# Atom_S3_Module_-_Rev_B.net
KiCad netlist of a schematic drawn in EAGLE
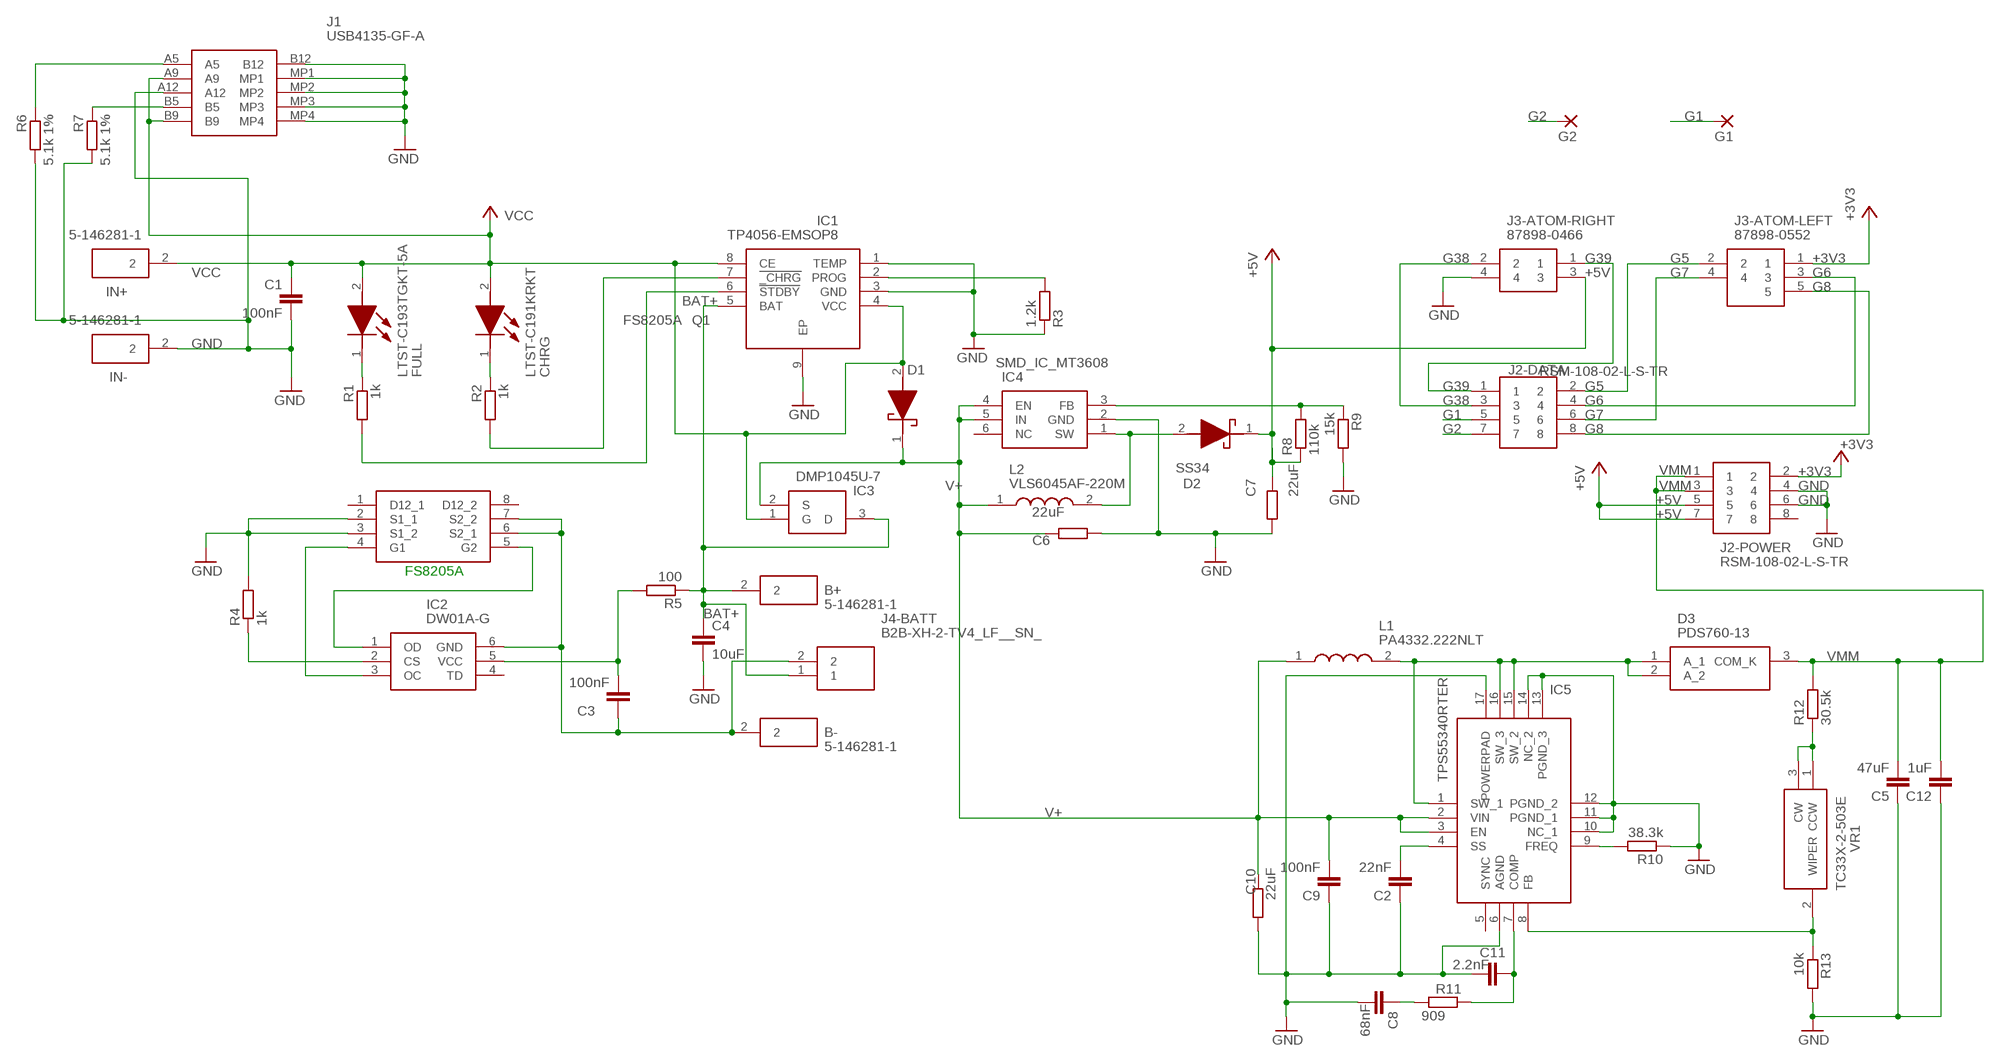
[diagram p0: schematic, sheet 1]

(export (version "E")
  (design (tool "Eeschema 10.0.6"))
  (components
    (comp (ref "B+")
      (value "5-146281-1")
      (footprint "eagle-import:51462811")
      (fields (field (name "MOUSER_PART_NUMBER") "571-5-146281-1"))
      (libsource (lib "eagle-import") (part "5-146281-1"))
    )
    (comp (ref "B-")
      (value "5-146281-1")
      (footprint "eagle-import:51462811")
      (fields (field (name "MOUSER_PART_NUMBER") "571-5-146281-1"))
      (libsource (lib "eagle-import") (part "5-146281-1"))
    )
    (comp (ref "C1")
      (value "100nF")
      (footprint "eagle-import:C0603")
      (libsource (lib "eagle-import") (part "C-EUC0603"))
    )
    (comp (ref "C2")
      (value "22nF")
      (footprint "eagle-import:C0603")
      (libsource (lib "eagle-import") (part "C-EUC0603"))
    )
    (comp (ref "C3")
      (value "100nF")
      (footprint "eagle-import:C0603")
      (libsource (lib "eagle-import") (part "C-EUC0603"))
    )
    (comp (ref "C4")
      (value "10uF")
      (footprint "eagle-import:C0603")
      (libsource (lib "eagle-import") (part "C-EUC0603"))
    )
    (comp (ref "C5")
      (value "47uF")
      (footprint "eagle-import:C1210")
      (libsource (lib "eagle-import") (part "C-EUC1210"))
    )
    (comp (ref "C6")
      (value "22uF")
      (footprint "eagle-import:R0805")
      (libsource (lib "eagle-import") (part "R-EU_R0805"))
    )
    (comp (ref "C7")
      (value "22uF")
      (footprint "eagle-import:R0805")
      (libsource (lib "eagle-import") (part "R-EU_R0805"))
    )
    (comp (ref "C8")
      (value "68nF")
      (footprint "eagle-import:C0603")
      (libsource (lib "eagle-import") (part "C-EUC0603"))
    )
    (comp (ref "C9")
      (value "100nF")
      (footprint "eagle-import:C0603")
      (libsource (lib "eagle-import") (part "C-EUC0603"))
    )
    (comp (ref "C10")
      (value "22uF")
      (footprint "eagle-import:R0805")
      (libsource (lib "eagle-import") (part "R-EU_R0805"))
    )
    (comp (ref "C11")
      (value "2.2nF")
      (footprint "eagle-import:C0603")
      (libsource (lib "eagle-import") (part "C-EUC0603"))
    )
    (comp (ref "C12")
      (value "1uF")
      (footprint "eagle-import:C0603")
      (libsource (lib "eagle-import") (part "C-EUC0603"))
    )
    (comp (ref "CHRG")
      (value "LTST-C191KRKT")
      (footprint "eagle-import:LEDC1608X55N")
      (fields (field (name "MOUSER_PART_NUMBER") "859-LTST-C191KRKT"))
      (libsource (lib "eagle-import") (part "LTST-C191KRKT"))
    )
    (comp (ref "D1")
      (value "SS34")
      (footprint "eagle-import:DIOM8059X256N")
      (fields (field (name "MOUSER_PART_NUMBER") "512-SS34"))
      (libsource (lib "eagle-import") (part "SS34"))
    )
    (comp (ref "D2")
      (value "SS34")
      (footprint "eagle-import:DIOM8059X256N")
      (fields (field (name "MOUSER_PART_NUMBER") "512-SS34"))
      (libsource (lib "eagle-import") (part "SS34"))
    )
    (comp (ref "D3")
      (value "PDS760-13")
      (footprint "eagle-import:PDS76013")
      (fields (field (name "MOUSER_PART_NUMBER") "621-PDS760-F"))
      (libsource (lib "eagle-import") (part "PDS760-13"))
    )
    (comp (ref "FULL")
      (value "LTST-C193TGKT-5A")
      (footprint "eagle-import:LEDC1608X45N")
      (fields (field (name "MOUSER_PART_NUMBER") "859-LTSTC193TGKT5A"))
      (libsource (lib "eagle-import") (part "LTST-C193TGKT-5A"))
    )
    (comp (ref "G1")
      (value "WIREPAD1,6/0,9")
      (footprint "eagle-import:1,6_0,9")
      (libsource (lib "eagle-import") (part "WIREPAD1,6/0,9"))
    )
    (comp (ref "G2")
      (value "WIREPAD1,6/0,9")
      (footprint "eagle-import:1,6_0,9")
      (libsource (lib "eagle-import") (part "WIREPAD1,6/0,9"))
    )
    (comp (ref "IC1")
      (value "TP4056-EMSOP8")
      (footprint "eagle-import:SOP65P490X110-9N")
      (libsource (lib "eagle-import") (part "TP4056-EMSOP8"))
    )
    (comp (ref "IC2")
      (value "DW01A-G")
      (footprint "eagle-import:SOT95P190X145-6N")
      (libsource (lib "eagle-import") (part "DW01A-G"))
    )
    (comp (ref "IC3")
      (value "DMP1045U-7")
      (footprint "eagle-import:SOT96P240X110-3N")
      (fields (field (name "MOUSER_PART_NUMBER") "621-DMP1045U-7"))
      (libsource (lib "eagle-import") (part "DMP1045U-7"))
    )
    (comp (ref "IC4")
      (value "SMD_IC_MT3608")
      (footprint "eagle-import:SOT95P280X145-6N")
      (fields
        (field (name "MANUFACTURER_PART_NUMBER") "SMD IC MT3608")
        (field (name "MOUSER_PART_NUMBER") "909-SMDICMT3608")
      )
      (libsource (lib "eagle-import") (part "SMD_IC_MT3608"))
    )
    (comp (ref "IC5")
      (value "TPS55340RTER")
      (footprint "eagle-import:QFN50P300X300X80-17N")
      (fields (field (name "MOUSER_PART_NUMBER") "595-TPS55340RTER"))
      (libsource (lib "eagle-import") (part "TPS55340RTER"))
    )
    (comp (ref "IN+")
      (value "5-146281-1")
      (footprint "eagle-import:51462811")
      (fields (field (name "MOUSER_PART_NUMBER") "571-5-146281-1"))
      (libsource (lib "eagle-import") (part "5-146281-1"))
    )
    (comp (ref "IN-")
      (value "5-146281-1")
      (footprint "eagle-import:51462811")
      (fields (field (name "MOUSER_PART_NUMBER") "571-5-146281-1"))
      (libsource (lib "eagle-import") (part "5-146281-1"))
    )
    (comp (ref "J1")
      (value "USB4135-GF-A")
      (footprint "eagle-import:USB4135GFA")
      (fields (field (name "MOUSER_PART_NUMBER") "640-USB4135-GF-A"))
      (libsource (lib "eagle-import") (part "USB4135-GF-A"))
    )
    (comp (ref "J2-DATA")
      (value "RSM-108-02-L-S-TR")
      (footprint "eagle-import:RSM10802LSTR")
      (fields (field (name "MOUSER_PART_NUMBER") "200-RSM10802LSTR"))
      (libsource (lib "eagle-import") (part "RSM-108-02-L-S-TR"))
    )
    (comp (ref "J2-POWER")
      (value "RSM-108-02-L-S-TR")
      (footprint "eagle-import:RSM10802LSTR")
      (fields (field (name "MOUSER_PART_NUMBER") "200-RSM10802LSTR"))
      (libsource (lib "eagle-import") (part "RSM-108-02-L-S-TR"))
    )
    (comp (ref "J3-ATOM-LEFT")
      (value "87898-0552")
      (footprint "eagle-import:878980552")
      (libsource (lib "eagle-import") (part "87898-0552"))
    )
    (comp (ref "J3-ATOM-RIGHT")
      (value "87898-0466")
      (footprint "eagle-import:878980466")
      (fields (field (name "MOUSER_PART_NUMBER") "538-87898-0466"))
      (libsource (lib "eagle-import") (part "87898-0466"))
    )
    (comp (ref "J4-BATT")
      (value "B2B-XH-2-TV4_LF__SN_")
      (footprint "eagle-import:B2BXH2TV4LFSN")
      (fields
        (field (name "MANUFACTURER_PART_NUMBER") "B2B-XH-2-TV4(LF)(SN)")
        (field (name "MOUSER_PART_NUMBER") "306-B2BXH2TV4LFSN")
      )
      (libsource (lib "eagle-import") (part "B2B-XH-2-TV4_LF__SN_"))
    )
    (comp (ref "L1")
      (value "PA4332.222NLT")
      (footprint "eagle-import:INDPM4042X200N")
      (fields (field (name "MOUSER_PART_NUMBER") "673-PA4332222NLT"))
      (libsource (lib "eagle-import") (part "PA4332.222NLT"))
    )
    (comp (ref "L2")
      (value "VLS6045AF-220M")
      (footprint "eagle-import:VLS6045")
      (fields (field (name "MOUSER_PART_NUMBER") "810-VLS6045AF-220M"))
      (libsource (lib "eagle-import") (part "VLS6045AF-220M"))
    )
    (comp (ref "Q1")
      (value "FS8205A")
      (footprint "eagle-import:SOP65P640X120-8N")
      (libsource (lib "eagle-import") (part "FS8205A"))
    )
    (comp (ref "R1")
      (value "1k")
      (footprint "eagle-import:R0603")
      (libsource (lib "eagle-import") (part "R-EU_R0603"))
    )
    (comp (ref "R2")
      (value "1k")
      (footprint "eagle-import:R0603")
      (libsource (lib "eagle-import") (part "R-EU_R0603"))
    )
    (comp (ref "R3")
      (value "1.2k")
      (footprint "eagle-import:R0603")
      (libsource (lib "eagle-import") (part "R-EU_R0603"))
    )
    (comp (ref "R4")
      (value "1k")
      (footprint "eagle-import:R0603")
      (libsource (lib "eagle-import") (part "R-EU_R0603"))
    )
    (comp (ref "R5")
      (value "100")
      (footprint "eagle-import:R0603")
      (libsource (lib "eagle-import") (part "R-EU_R0603"))
    )
    (comp (ref "R6")
      (value "5.1k 1%")
      (footprint "eagle-import:R0603")
      (libsource (lib "eagle-import") (part "R-EU_R0603"))
    )
    (comp (ref "R7")
      (value "5.1k 1%")
      (footprint "eagle-import:R0603")
      (libsource (lib "eagle-import") (part "R-EU_R0603"))
    )
    (comp (ref "R8")
      (value "110k")
      (footprint "eagle-import:R0603")
      (libsource (lib "eagle-import") (part "R-EU_R0603"))
    )
    (comp (ref "R9")
      (value "15k")
      (footprint "eagle-import:R0603")
      (libsource (lib "eagle-import") (part "R-EU_R0603"))
    )
    (comp (ref "R10")
      (value "38.3k")
      (footprint "eagle-import:R0603")
      (libsource (lib "eagle-import") (part "R-EU_R0603"))
    )
    (comp (ref "R11")
      (value "909")
      (footprint "eagle-import:R0603")
      (libsource (lib "eagle-import") (part "R-EU_R0603"))
    )
    (comp (ref "R12")
      (value "30.5k")
      (footprint "eagle-import:R0805")
      (libsource (lib "eagle-import") (part "R-EU_R0805"))
    )
    (comp (ref "R13")
      (value "10k")
      (footprint "eagle-import:R0603")
      (libsource (lib "eagle-import") (part "R-EU_R0603"))
    )
    (comp (ref "VR1")
      (value "TC33X-2-503E")
      (footprint "eagle-import:TC33X2503E")
      (fields (field (name "MOUSER_PART_NUMBER") "652-TC33X-2-503E"))
      (libsource (lib "eagle-import") (part "TC33X-2-503E"))
    )
  )
  (nets
    (net (code "1") (name "+3V3") (class "Default")
      (node (ref "J2-POWER") (pin "2") (pinfunction "2_2") (pintype "bidirectional"))
      (node (ref "J3-ATOM-LEFT") (pin "1") (pinfunction "1_1") (pintype "bidirectional"))
    )
    (net (code "2") (name "+5V") (class "Default")
      (node (ref "C7") (pin "2") (pinfunction "2_2") (pintype "passive"))
      (node (ref "D2") (pin "1") (pinfunction "K_1") (pintype "bidirectional"))
      (node (ref "J2-POWER") (pin "5") (pinfunction "5_5") (pintype "bidirectional"))
      (node (ref "J2-POWER") (pin "7") (pinfunction "7_7") (pintype "bidirectional"))
      (node (ref "J3-ATOM-RIGHT") (pin "3") (pinfunction "3_3") (pintype "bidirectional"))
      (node (ref "R8") (pin "1") (pinfunction "1_1") (pintype "passive"))
    )
    (net (code "3") (name "BAT+") (class "Default")
      (node (ref "B+") (pin "2") (pinfunction "2_2") (pintype "bidirectional"))
      (node (ref "C4") (pin "1") (pinfunction "1_1") (pintype "passive"))
      (node (ref "IC1") (pin "5") (pinfunction "BAT_5") (pintype "bidirectional"))
      (node (ref "IC3") (pin "3") (pinfunction "D_3") (pintype "bidirectional"))
      (node (ref "J4-BATT") (pin "1") (pinfunction "1_1") (pintype "bidirectional"))
      (node (ref "R5") (pin "1") (pinfunction "1_1") (pintype "passive"))
    )
    (net (code "4") (name "G1") (class "Default")
      (node (ref "G1") (pin "1") (pinfunction "P_1") (pintype "passive"))
      (node (ref "J2-DATA") (pin "5") (pinfunction "5_5") (pintype "bidirectional"))
    )
    (net (code "5") (name "G2") (class "Default")
      (node (ref "G2") (pin "1") (pinfunction "P_1") (pintype "passive"))
      (node (ref "J2-DATA") (pin "7") (pinfunction "7_7") (pintype "bidirectional"))
    )
    (net (code "6") (name "G5") (class "Default")
      (node (ref "J2-DATA") (pin "2") (pinfunction "2_2") (pintype "bidirectional"))
      (node (ref "J3-ATOM-LEFT") (pin "2") (pinfunction "2_2") (pintype "bidirectional"))
    )
    (net (code "7") (name "G6") (class "Default")
      (node (ref "J2-DATA") (pin "4") (pinfunction "4_4") (pintype "bidirectional"))
      (node (ref "J3-ATOM-LEFT") (pin "3") (pinfunction "3_3") (pintype "bidirectional"))
    )
    (net (code "8") (name "G7") (class "Default")
      (node (ref "J2-DATA") (pin "6") (pinfunction "6_6") (pintype "bidirectional"))
      (node (ref "J3-ATOM-LEFT") (pin "4") (pinfunction "4_4") (pintype "bidirectional"))
    )
    (net (code "9") (name "G8") (class "Default")
      (node (ref "J2-DATA") (pin "8") (pinfunction "8_8") (pintype "bidirectional"))
      (node (ref "J3-ATOM-LEFT") (pin "5") (pinfunction "5_5") (pintype "bidirectional"))
    )
    (net (code "10") (name "G38") (class "Default")
      (node (ref "J2-DATA") (pin "3") (pinfunction "3_3") (pintype "bidirectional"))
      (node (ref "J3-ATOM-RIGHT") (pin "2") (pinfunction "2_2") (pintype "bidirectional"))
    )
    (net (code "11") (name "G39") (class "Default")
      (node (ref "J2-DATA") (pin "1") (pinfunction "1_1") (pintype "bidirectional"))
      (node (ref "J3-ATOM-RIGHT") (pin "1") (pinfunction "1_1") (pintype "bidirectional"))
    )
    (net (code "12") (name "GND") (class "Default")
      (node (ref "C1") (pin "2") (pinfunction "2_2") (pintype "passive"))
      (node (ref "C10") (pin "1") (pinfunction "1_1") (pintype "passive"))
      (node (ref "C11") (pin "2") (pinfunction "2_2") (pintype "passive"))
      (node (ref "C12") (pin "1") (pinfunction "1_1") (pintype "passive"))
      (node (ref "C2") (pin "1") (pinfunction "1_1") (pintype "passive"))
      (node (ref "C4") (pin "2") (pinfunction "2_2") (pintype "passive"))
      (node (ref "C5") (pin "1") (pinfunction "1_1") (pintype "passive"))
      (node (ref "C6") (pin "1") (pinfunction "1_1") (pintype "passive"))
      (node (ref "C7") (pin "1") (pinfunction "1_1") (pintype "passive"))
      (node (ref "C8") (pin "2") (pinfunction "2_2") (pintype "passive"))
      (node (ref "C9") (pin "1") (pinfunction "1_1") (pintype "passive"))
      (node (ref "IC1") (pin "1") (pinfunction "TEMP_1") (pintype "bidirectional"))
      (node (ref "IC1") (pin "3") (pinfunction "GND_3") (pintype "bidirectional"))
      (node (ref "IC1") (pin "9") (pinfunction "EP_9") (pintype "bidirectional"))
      (node (ref "IC4") (pin "2") (pinfunction "GND_2") (pintype "bidirectional"))
      (node (ref "IC5") (pin "10") (pinfunction "NC_1_10") (pintype "bidirectional"))
      (node (ref "IC5") (pin "11") (pinfunction "PGND_1_11") (pintype "bidirectional"))
      (node (ref "IC5") (pin "12") (pinfunction "PGND_2_12") (pintype "bidirectional"))
      (node (ref "IC5") (pin "13") (pinfunction "PGND_3_13") (pintype "bidirectional"))
      (node (ref "IC5") (pin "14") (pinfunction "NC_2_14") (pintype "bidirectional"))
      (node (ref "IC5") (pin "17") (pinfunction "POWERPAD_17") (pintype "bidirectional"))
      (node (ref "IC5") (pin "6") (pinfunction "AGND_6") (pintype "bidirectional"))
      (node (ref "IN-") (pin "2") (pinfunction "2_2") (pintype "bidirectional"))
      (node (ref "J1") (pin "A12") (pinfunction "A12_A12") (pintype "bidirectional"))
      (node (ref "J1") (pin "B12") (pinfunction "B12_B12") (pintype "bidirectional"))
      (node (ref "J1") (pin "MP1") (pinfunction "MP1_MP1") (pintype "bidirectional"))
      (node (ref "J1") (pin "MP2") (pinfunction "MP2_MP2") (pintype "bidirectional"))
      (node (ref "J1") (pin "MP3") (pinfunction "MP3_MP3") (pintype "bidirectional"))
      (node (ref "J1") (pin "MP4") (pinfunction "MP4_MP4") (pintype "bidirectional"))
      (node (ref "J2-POWER") (pin "4") (pinfunction "4_4") (pintype "bidirectional"))
      (node (ref "J2-POWER") (pin "6") (pinfunction "6_6") (pintype "bidirectional"))
      (node (ref "J3-ATOM-RIGHT") (pin "4") (pinfunction "4_4") (pintype "bidirectional"))
      (node (ref "Q1") (pin "2") (pinfunction "S1_1_2") (pintype "bidirectional"))
      (node (ref "Q1") (pin "3") (pinfunction "S1_2_3") (pintype "bidirectional"))
      (node (ref "R10") (pin "1") (pinfunction "1_1") (pintype "passive"))
      (node (ref "R13") (pin "2") (pinfunction "2_2") (pintype "passive"))
      (node (ref "R3") (pin "1") (pinfunction "1_1") (pintype "passive"))
      (node (ref "R4") (pin "2") (pinfunction "2_2") (pintype "passive"))
      (node (ref "R6") (pin "2") (pinfunction "2_2") (pintype "passive"))
      (node (ref "R7") (pin "2") (pinfunction "2_2") (pintype "passive"))
      (node (ref "R9") (pin "2") (pinfunction "2_2") (pintype "passive"))
    )
    (net (code "13") (name "Net-(C8-Pad1)") (class "Default")
      (node (ref "C8") (pin "1") (pinfunction "1_1") (pintype "passive"))
      (node (ref "R11") (pin "1") (pinfunction "1_1") (pintype "passive"))
    )
    (net (code "14") (name "Net-(CHRG-K)") (class "Default")
      (node (ref "CHRG") (pin "1") (pinfunction "K_1") (pintype "bidirectional"))
      (node (ref "R2") (pin "1") (pinfunction "1_1") (pintype "passive"))
    )
    (net (code "15") (name "Net-(D2-A)") (class "Default")
      (node (ref "D2") (pin "2") (pinfunction "A_2") (pintype "bidirectional"))
      (node (ref "IC4") (pin "1") (pinfunction "SW_1") (pintype "bidirectional"))
      (node (ref "L2") (pin "2") (pinfunction "2_2") (pintype "bidirectional"))
    )
    (net (code "16") (name "Net-(D3-A_1)") (class "Default")
      (node (ref "D3") (pin "1") (pinfunction "A_1_1") (pintype "bidirectional"))
      (node (ref "D3") (pin "2") (pinfunction "A_2_2") (pintype "bidirectional"))
      (node (ref "IC5") (pin "1") (pinfunction "SW_1_1") (pintype "bidirectional"))
      (node (ref "IC5") (pin "15") (pinfunction "SW_2_15") (pintype "bidirectional"))
      (node (ref "IC5") (pin "16") (pinfunction "SW_3_16") (pintype "bidirectional"))
      (node (ref "L1") (pin "2") (pinfunction "2_2") (pintype "bidirectional"))
    )
    (net (code "17") (name "Net-(FULL-K)") (class "Default")
      (node (ref "FULL") (pin "1") (pinfunction "K_1") (pintype "bidirectional"))
      (node (ref "R1") (pin "1") (pinfunction "1_1") (pintype "passive"))
    )
    (net (code "18") (name "Net-(IC1-PROG)") (class "Default")
      (node (ref "IC1") (pin "2") (pinfunction "PROG_2") (pintype "bidirectional"))
      (node (ref "R3") (pin "2") (pinfunction "2_2") (pintype "passive"))
    )
    (net (code "19") (name "Net-(IC1-~{STDBY})") (class "Default")
      (node (ref "IC1") (pin "6") (pinfunction "~{STDBY}_6") (pintype "bidirectional"))
      (node (ref "R1") (pin "2") (pinfunction "2_2") (pintype "passive"))
    )
    (net (code "20") (name "Net-(IC1-~{_CHRG})") (class "Default")
      (node (ref "IC1") (pin "7") (pinfunction "~{_CHRG}_7") (pintype "bidirectional"))
      (node (ref "R2") (pin "2") (pinfunction "2_2") (pintype "passive"))
    )
    (net (code "21") (name "Net-(IC2-CS)") (class "Default")
      (node (ref "IC2") (pin "2") (pinfunction "CS_2") (pintype "bidirectional"))
      (node (ref "R4") (pin "1") (pinfunction "1_1") (pintype "passive"))
    )
    (net (code "22") (name "Net-(IC2-GND)") (class "Default")
      (node (ref "B-") (pin "2") (pinfunction "2_2") (pintype "bidirectional"))
      (node (ref "C3") (pin "1") (pinfunction "1_1") (pintype "passive"))
      (node (ref "IC2") (pin "6") (pinfunction "GND_6") (pintype "bidirectional"))
      (node (ref "J4-BATT") (pin "2") (pinfunction "2_2") (pintype "bidirectional"))
      (node (ref "Q1") (pin "6") (pinfunction "S2_1_6") (pintype "bidirectional"))
      (node (ref "Q1") (pin "7") (pinfunction "S2_2_7") (pintype "bidirectional"))
    )
    (net (code "23") (name "Net-(IC2-OC)") (class "Default")
      (node (ref "IC2") (pin "3") (pinfunction "OC_3") (pintype "bidirectional"))
      (node (ref "Q1") (pin "4") (pinfunction "G1_4") (pintype "bidirectional"))
    )
    (net (code "24") (name "Net-(IC2-OD)") (class "Default")
      (node (ref "IC2") (pin "1") (pinfunction "OD_1") (pintype "bidirectional"))
      (node (ref "Q1") (pin "5") (pinfunction "G2_5") (pintype "bidirectional"))
    )
    (net (code "25") (name "Net-(IC2-VCC)") (class "Default")
      (node (ref "C3") (pin "2") (pinfunction "2_2") (pintype "passive"))
      (node (ref "IC2") (pin "5") (pinfunction "VCC_5") (pintype "bidirectional"))
      (node (ref "R5") (pin "2") (pinfunction "2_2") (pintype "passive"))
    )
    (net (code "26") (name "Net-(IC4-FB)") (class "Default")
      (node (ref "IC4") (pin "3") (pinfunction "FB_3") (pintype "bidirectional"))
      (node (ref "R8") (pin "2") (pinfunction "2_2") (pintype "passive"))
      (node (ref "R9") (pin "1") (pinfunction "1_1") (pintype "passive"))
    )
    (net (code "27") (name "Net-(IC5-COMP)") (class "Default")
      (node (ref "C11") (pin "1") (pinfunction "1_1") (pintype "passive"))
      (node (ref "IC5") (pin "7") (pinfunction "COMP_7") (pintype "bidirectional"))
      (node (ref "R11") (pin "2") (pinfunction "2_2") (pintype "passive"))
    )
    (net (code "28") (name "Net-(IC5-FB)") (class "Default")
      (node (ref "IC5") (pin "8") (pinfunction "FB_8") (pintype "bidirectional"))
      (node (ref "R13") (pin "1") (pinfunction "1_1") (pintype "passive"))
      (node (ref "VR1") (pin "2") (pinfunction "WIPER_2") (pintype "bidirectional"))
    )
    (net (code "29") (name "Net-(IC5-FREQ)") (class "Default")
      (node (ref "IC5") (pin "9") (pinfunction "FREQ_9") (pintype "bidirectional"))
      (node (ref "R10") (pin "2") (pinfunction "2_2") (pintype "passive"))
    )
    (net (code "30") (name "Net-(IC5-SS)") (class "Default")
      (node (ref "C2") (pin "2") (pinfunction "2_2") (pintype "passive"))
      (node (ref "IC5") (pin "4") (pinfunction "SS_4") (pintype "bidirectional"))
    )
    (net (code "31") (name "Net-(J1-PadA5)") (class "Default")
      (node (ref "J1") (pin "A5") (pinfunction "A5_A5") (pintype "bidirectional"))
      (node (ref "R6") (pin "1") (pinfunction "1_1") (pintype "passive"))
    )
    (net (code "32") (name "Net-(J1-PadB5)") (class "Default")
      (node (ref "J1") (pin "B5") (pinfunction "B5_B5") (pintype "bidirectional"))
      (node (ref "R7") (pin "1") (pinfunction "1_1") (pintype "passive"))
    )
    (net (code "33") (name "Net-(VR1-CCW)") (class "Default")
      (node (ref "R12") (pin "1") (pinfunction "1_1") (pintype "passive"))
      (node (ref "VR1") (pin "1") (pinfunction "CCW_1") (pintype "bidirectional"))
      (node (ref "VR1") (pin "3") (pinfunction "CW_3") (pintype "bidirectional"))
    )
    (net (code "34") (name "V+") (class "Default")
      (node (ref "C10") (pin "2") (pinfunction "2_2") (pintype "passive"))
      (node (ref "C6") (pin "2") (pinfunction "2_2") (pintype "passive"))
      (node (ref "C9") (pin "2") (pinfunction "2_2") (pintype "passive"))
      (node (ref "D1") (pin "1") (pinfunction "K_1") (pintype "bidirectional"))
      (node (ref "IC3") (pin "2") (pinfunction "S_2") (pintype "bidirectional"))
      (node (ref "IC4") (pin "4") (pinfunction "EN_4") (pintype "bidirectional"))
      (node (ref "IC4") (pin "5") (pinfunction "IN_5") (pintype "bidirectional"))
      (node (ref "IC5") (pin "2") (pinfunction "VIN_2") (pintype "bidirectional"))
      (node (ref "IC5") (pin "3") (pinfunction "EN_3") (pintype "bidirectional"))
      (node (ref "L1") (pin "1") (pinfunction "1_1") (pintype "bidirectional"))
      (node (ref "L2") (pin "1") (pinfunction "1_1") (pintype "bidirectional"))
    )
    (net (code "35") (name "VCC") (class "Default")
      (node (ref "C1") (pin "1") (pinfunction "1_1") (pintype "passive"))
      (node (ref "CHRG") (pin "2") (pinfunction "A_2") (pintype "bidirectional"))
      (node (ref "D1") (pin "2") (pinfunction "A_2") (pintype "bidirectional"))
      (node (ref "FULL") (pin "2") (pinfunction "A_2") (pintype "bidirectional"))
      (node (ref "IC1") (pin "4") (pinfunction "VCC_4") (pintype "bidirectional"))
      (node (ref "IC1") (pin "8") (pinfunction "CE_8") (pintype "bidirectional"))
      (node (ref "IC3") (pin "1") (pinfunction "G_1") (pintype "bidirectional"))
      (node (ref "IN+") (pin "2") (pinfunction "2_2") (pintype "bidirectional"))
      (node (ref "J1") (pin "A9") (pinfunction "A9_A9") (pintype "bidirectional"))
      (node (ref "J1") (pin "B9") (pinfunction "B9_B9") (pintype "bidirectional"))
    )
    (net (code "36") (name "VMM") (class "Default")
      (node (ref "C12") (pin "2") (pinfunction "2_2") (pintype "passive"))
      (node (ref "C5") (pin "2") (pinfunction "2_2") (pintype "passive"))
      (node (ref "D3") (pin "3") (pinfunction "COM_K_3") (pintype "bidirectional"))
      (node (ref "J2-POWER") (pin "1") (pinfunction "1_1") (pintype "bidirectional"))
      (node (ref "J2-POWER") (pin "3") (pinfunction "3_3") (pintype "bidirectional"))
      (node (ref "R12") (pin "2") (pinfunction "2_2") (pintype "passive"))
    )
    (net (code "37") (name "unconnected-(IC2-TD-Pad4)") (class "Default")
      (node (ref "IC2") (pin "4") (pinfunction "TD_4") (pintype "bidirectional"))
    )
    (net (code "38") (name "unconnected-(IC4-NC-Pad6)") (class "Default")
      (node (ref "IC4") (pin "6") (pinfunction "NC_6") (pintype "no_connect"))
    )
    (net (code "39") (name "unconnected-(IC5-SYNC-Pad5)") (class "Default")
      (node (ref "IC5") (pin "5") (pinfunction "SYNC_5") (pintype "bidirectional"))
    )
    (net (code "40") (name "unconnected-(J2-POWER-Pad8)") (class "Default")
      (node (ref "J2-POWER") (pin "8") (pinfunction "8_8") (pintype "bidirectional"))
    )
    (net (code "41") (name "unconnected-(Q1-D12_1-Pad1)") (class "Default")
      (node (ref "Q1") (pin "1") (pinfunction "D12_1_1") (pintype "bidirectional"))
    )
    (net (code "42") (name "unconnected-(Q1-D12_2-Pad8)") (class "Default")
      (node (ref "Q1") (pin "8") (pinfunction "D12_2_8") (pintype "bidirectional"))
    )
  )
)
